# controller.net
KiCad netlist of a schematic drawn in Altium Designer
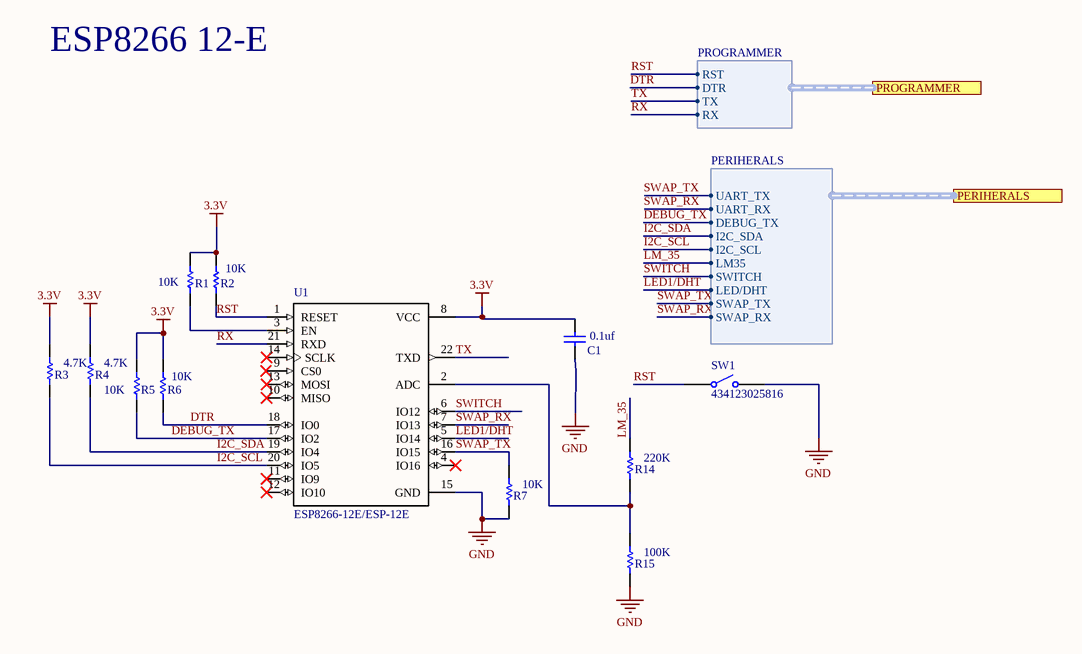
[diagram p0: controller.SchDoc]

(export (version "E")
  (design (tool "Eeschema 10.0.6"))
  (components
    (comp (ref "C1")
      (value "0.1uf")
      (footprint "CAPC0603")
      (fields
        (field (name "PART NUMBER") "08055C104KAJ2A")
        (field (name "MANUFACTURER") "AVX Interconnect / Elco")
      )
      (libsource (lib "Miscellaneous Devices") (part "CAP"))
    )
    (comp (ref "R1")
      (value "10K")
      (footprint "RESC0603")
      (description "2R55 0.125W 1% 0805 (2012 Metric)  SMD")
      (fields (field (name "TOLERANCE") "1 %") (field (name "POWER") "0.125 W"))
      (libsource (lib "Components - 22.01.19 - 11.39") (part "RES"))
    )
    (comp (ref "R2")
      (value "10K")
      (footprint "RESC0603")
      (description "2R55 0.125W 1% 0805 (2012 Metric)  SMD")
      (fields (field (name "TOLERANCE") "1 %") (field (name "POWER") "0.125 W"))
      (libsource (lib "Components - 22.01.19 - 11.39") (part "RES"))
    )
    (comp (ref "R3")
      (value "4.7K")
      (footprint "RESC0603")
      (description "2R55 0.125W 1% 0805 (2012 Metric)  SMD")
      (fields (field (name "TOLERANCE") "1 %") (field (name "POWER") "0.125 W"))
      (libsource (lib "Components - 22.01.19 - 11.39") (part "RES"))
    )
    (comp (ref "R4")
      (value "4.7K")
      (footprint "RESC0603")
      (description "2R55 0.125W 1% 0805 (2012 Metric)  SMD")
      (fields (field (name "TOLERANCE") "1 %") (field (name "POWER") "0.125 W"))
      (libsource (lib "Components - 22.01.19 - 11.39") (part "RES"))
    )
    (comp (ref "R5")
      (value "10K")
      (footprint "RESC0603")
      (description "2R55 0.125W 1% 0805 (2012 Metric)  SMD")
      (fields (field (name "TOLERANCE") "1 %") (field (name "POWER") "0.125 W"))
      (libsource (lib "Components - 22.01.19 - 11.39") (part "RES"))
    )
    (comp (ref "R6")
      (value "10K")
      (footprint "RESC0603")
      (description "2R55 0.125W 1% 0805 (2012 Metric)  SMD")
      (fields (field (name "TOLERANCE") "1 %") (field (name "POWER") "0.125 W"))
      (libsource (lib "Components - 22.01.19 - 11.39") (part "RES"))
    )
    (comp (ref "R7")
      (value "10K")
      (footprint "RESC0603")
      (description "2R55 0.125W 1% 0805 (2012 Metric)  SMD")
      (fields (field (name "TOLERANCE") "1 %") (field (name "POWER") "0.125 W"))
      (libsource (lib "Components - 22.01.19 - 11.39") (part "RES"))
    )
    (comp (ref "R14")
      (value "220K")
      (footprint "RESC0603")
      (description "2R55 0.125W 1% 0805 (2012 Metric)  SMD")
      (fields (field (name "TOLERANCE") "1 %") (field (name "POWER") "0.125 W"))
      (libsource (lib "Components - 22.01.19 - 11.39") (part "RES"))
    )
    (comp (ref "R15")
      (value "100K")
      (footprint "RESC0603")
      (description "2R55 0.125W 1% 0805 (2012 Metric)  SMD")
      (fields (field (name "TOLERANCE") "1 %") (field (name "POWER") "0.125 W"))
      (libsource (lib "Components - 22.01.19 - 11.39") (part "RES"))
    )
    (comp (ref "SW1")
      (value "434123025816")
      (footprint "434123025816")
      (description "WS-TASV J-Bend SMD Tact Switch 6.0X3.8 mm")
      (fields (field (name "MANUFACTURER") "Wuerth Elektronik"))
      (libsource (lib "Altium Content Vault") (part "WE-TACT-SW-2"))
    )
    (comp (ref "U1")
      (value "ESP8266-12E/ESP-12E")
      (footprint "*XCVR_ESP8266-12E/ESP-12E")
      (fields (field (name "MF") "AI-Thinker"))
      (libsource (lib "ESP8266-12E_ESP-12E") (part "ESP8266-12E/ESP-12E"))
    )
  )
  (nets
    (net (code "3") (name "/DEBUG_TX") (class "Default")
      (node (ref "R5") (pin "1") (pinfunction "1_1") (pintype "passive"))
      (node (ref "U1") (pin "17") (pinfunction "IO2_17") (pintype "bidirectional"))
    )
    (net (code "4") (name "/DTR") (class "Default")
      (node (ref "R6") (pin "1") (pinfunction "1_1") (pintype "passive"))
      (node (ref "U1") (pin "18") (pinfunction "IO0_18") (pintype "bidirectional"))
    )
    (net (code "5") (name "/I2C_SCL") (class "Default")
      (node (ref "R3") (pin "1") (pinfunction "1_1") (pintype "passive"))
      (node (ref "U1") (pin "20") (pinfunction "IO5_20") (pintype "bidirectional"))
    )
    (net (code "6") (name "/I2C_SDA") (class "Default")
      (node (ref "R4") (pin "1") (pinfunction "1_1") (pintype "passive"))
      (node (ref "U1") (pin "19") (pinfunction "IO4_19") (pintype "bidirectional"))
    )
    (net (code "7") (name "/LED1{slash}DHT") (class "Default")
      (node (ref "U1") (pin "5") (pinfunction "IO14_5") (pintype "bidirectional"))
    )
    (net (code "8") (name "/LM_35") (class "Default")
      (node (ref "R14") (pin "2") (pinfunction "2_2") (pintype "passive"))
    )
    (net (code "9") (name "/RST") (class "Default")
      (node (ref "R2") (pin "1") (pinfunction "1_1") (pintype "passive"))
      (node (ref "SW1") (pin "1") (pinfunction "1_1") (pintype "passive"))
      (node (ref "U1") (pin "1") (pinfunction "RESET_1") (pintype "input"))
    )
    (net (code "10") (name "/RX") (class "Default")
      (node (ref "U1") (pin "21") (pinfunction "RXD_21") (pintype "input"))
    )
    (net (code "11") (name "/SWAP_RX") (class "Default")
      (node (ref "U1") (pin "7") (pinfunction "IO13_7") (pintype "bidirectional"))
    )
    (net (code "12") (name "/SWAP_TX") (class "Default")
      (node (ref "R7") (pin "2") (pinfunction "2_2") (pintype "passive"))
      (node (ref "U1") (pin "16") (pinfunction "IO15_16") (pintype "bidirectional"))
    )
    (net (code "13") (name "/SWITCH") (class "Default")
      (node (ref "U1") (pin "6") (pinfunction "IO12_6") (pintype "bidirectional"))
    )
    (net (code "14") (name "/TX") (class "Default")
      (node (ref "U1") (pin "22") (pinfunction "TXD_22") (pintype "output"))
    )
    (net (code "17") (name "3.3V") (class "Default")
      (node (ref "C1") (pin "1") (pinfunction "1_1") (pintype "passive"))
      (node (ref "R1") (pin "2") (pinfunction "2_2") (pintype "passive"))
      (node (ref "R2") (pin "2") (pinfunction "2_2") (pintype "passive"))
      (node (ref "R3") (pin "2") (pinfunction "2_2") (pintype "passive"))
      (node (ref "R4") (pin "2") (pinfunction "2_2") (pintype "passive"))
      (node (ref "R5") (pin "2") (pinfunction "2_2") (pintype "passive"))
      (node (ref "R6") (pin "2") (pinfunction "2_2") (pintype "passive"))
      (node (ref "U1") (pin "8") (pinfunction "VCC_8") (pintype "power_in"))
    )
    (net (code "18") (name "GND") (class "Default")
      (node (ref "C1") (pin "2") (pinfunction "2_2") (pintype "passive"))
      (node (ref "R15") (pin "1") (pinfunction "1_1") (pintype "passive"))
      (node (ref "R7") (pin "1") (pinfunction "1_1") (pintype "passive"))
      (node (ref "SW1") (pin "2") (pinfunction "2_2") (pintype "passive"))
      (node (ref "U1") (pin "15") (pinfunction "GND_15") (pintype "power_in"))
    )
    (net (code "19") (name "Net-(U1-ADC)") (class "Default")
      (node (ref "R14") (pin "1") (pinfunction "1_1") (pintype "passive"))
      (node (ref "R15") (pin "2") (pinfunction "2_2") (pintype "passive"))
      (node (ref "U1") (pin "2") (pinfunction "ADC_2") (pintype "passive"))
    )
    (net (code "20") (name "Net-(U1-EN)") (class "Default")
      (node (ref "R1") (pin "1") (pinfunction "1_1") (pintype "passive"))
      (node (ref "U1") (pin "3") (pinfunction "EN_3") (pintype "input"))
    )
    (net (code "21") (name "unconnected-(U1-CS0-Pad9)") (class "Default")
      (node (ref "U1") (pin "9") (pinfunction "CS0_9") (pintype "input"))
    )
    (net (code "22") (name "unconnected-(U1-IO9-Pad11)") (class "Default")
      (node (ref "U1") (pin "11") (pinfunction "IO9_11") (pintype "bidirectional+no_connect"))
    )
    (net (code "23") (name "unconnected-(U1-IO10-Pad12)") (class "Default")
      (node (ref "U1") (pin "12") (pinfunction "IO10_12") (pintype "bidirectional+no_connect"))
    )
    (net (code "24") (name "unconnected-(U1-IO16-Pad4)") (class "Default")
      (node (ref "U1") (pin "4") (pinfunction "IO16_4") (pintype "bidirectional+no_connect"))
    )
    (net (code "25") (name "unconnected-(U1-MISO-Pad10)") (class "Default")
      (node (ref "U1") (pin "10") (pinfunction "MISO_10") (pintype "bidirectional+no_connect"))
    )
    (net (code "26") (name "unconnected-(U1-MOSI-Pad13)") (class "Default")
      (node (ref "U1") (pin "13") (pinfunction "MOSI_13") (pintype "bidirectional+no_connect"))
    )
    (net (code "27") (name "unconnected-(U1-SCLK-Pad14)") (class "Default")
      (node (ref "U1") (pin "14") (pinfunction "SCLK_14") (pintype "input+no_connect"))
    )
  )
)
